# TFT_Adapter_Board.net
KiCad netlist of a schematic drawn in Altium Designer
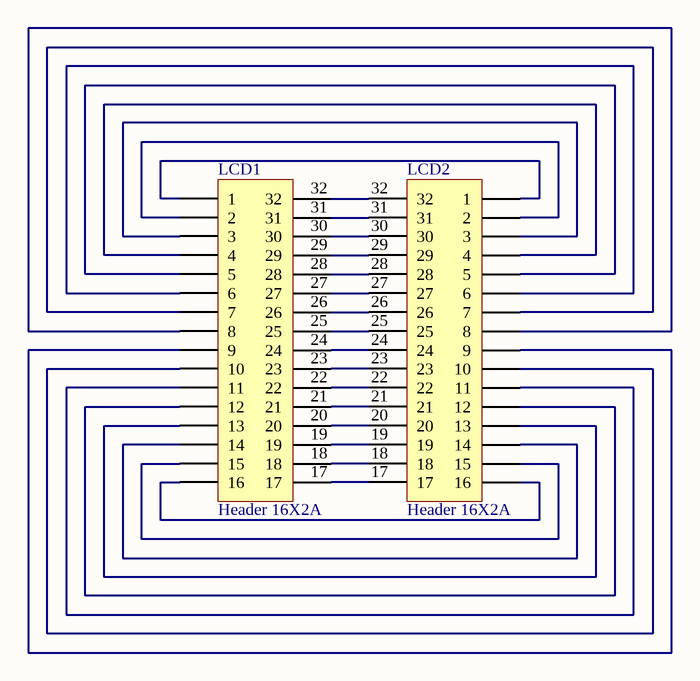
[diagram p0: TFT_Adapter_Board.SchDoc]

(export (version "E")
  (design (tool "Eeschema 10.0.6"))
  (components
    (comp (ref "LCD1")
      (value "Header 16X2A")
      (footprint "HDR2X16_CEN")
      (description "Header, 16-Pin, Dual row")
      (fields (field (name "PUBLISHER") "Altium Limited"))
      (libsource (lib "Peace的集成库") (part "Header 16X2A"))
    )
    (comp (ref "LCD2")
      (value "Header 16X2A")
      (footprint "HDR2X16_CEN")
      (description "Header, 16-Pin, Dual row")
      (fields (field (name "PUBLISHER") "Altium Limited"))
      (libsource (lib "") (part "Header 16X2A_1"))
    )
  )
  (nets
    (net (code "1") (name "Net-(LCD1-Pad1)") (class "Default")
      (node (ref "LCD1") (pin "1") (pinfunction "1_1") (pintype "passive"))
      (node (ref "LCD2") (pin "1") (pinfunction "1_1") (pintype "passive"))
    )
    (net (code "2") (name "Net-(LCD1-Pad2)") (class "Default")
      (node (ref "LCD1") (pin "2") (pinfunction "2_2") (pintype "passive"))
      (node (ref "LCD2") (pin "2") (pinfunction "2_2") (pintype "passive"))
    )
    (net (code "3") (name "Net-(LCD1-Pad3)") (class "Default")
      (node (ref "LCD1") (pin "3") (pinfunction "3_3") (pintype "passive"))
      (node (ref "LCD2") (pin "3") (pinfunction "3_3") (pintype "passive"))
    )
    (net (code "4") (name "Net-(LCD1-Pad4)") (class "Default")
      (node (ref "LCD1") (pin "4") (pinfunction "4_4") (pintype "passive"))
      (node (ref "LCD2") (pin "4") (pinfunction "4_4") (pintype "passive"))
    )
    (net (code "5") (name "Net-(LCD1-Pad5)") (class "Default")
      (node (ref "LCD1") (pin "5") (pinfunction "5_5") (pintype "passive"))
      (node (ref "LCD2") (pin "5") (pinfunction "5_5") (pintype "passive"))
    )
    (net (code "6") (name "Net-(LCD1-Pad6)") (class "Default")
      (node (ref "LCD1") (pin "6") (pinfunction "6_6") (pintype "passive"))
      (node (ref "LCD2") (pin "6") (pinfunction "6_6") (pintype "passive"))
    )
    (net (code "7") (name "Net-(LCD1-Pad7)") (class "Default")
      (node (ref "LCD1") (pin "7") (pinfunction "7_7") (pintype "passive"))
      (node (ref "LCD2") (pin "7") (pinfunction "7_7") (pintype "passive"))
    )
    (net (code "8") (name "Net-(LCD1-Pad8)") (class "Default")
      (node (ref "LCD1") (pin "8") (pinfunction "8_8") (pintype "passive"))
      (node (ref "LCD2") (pin "8") (pinfunction "8_8") (pintype "passive"))
    )
    (net (code "9") (name "Net-(LCD1-Pad9)") (class "Default")
      (node (ref "LCD1") (pin "9") (pinfunction "9_9") (pintype "passive"))
      (node (ref "LCD2") (pin "9") (pinfunction "9_9") (pintype "passive"))
    )
    (net (code "10") (name "Net-(LCD1-Pad10)") (class "Default")
      (node (ref "LCD1") (pin "10") (pinfunction "10_10") (pintype "passive"))
      (node (ref "LCD2") (pin "10") (pinfunction "10_10") (pintype "passive"))
    )
    (net (code "11") (name "Net-(LCD1-Pad11)") (class "Default")
      (node (ref "LCD1") (pin "11") (pinfunction "11_11") (pintype "passive"))
      (node (ref "LCD2") (pin "11") (pinfunction "11_11") (pintype "passive"))
    )
    (net (code "12") (name "Net-(LCD1-Pad12)") (class "Default")
      (node (ref "LCD1") (pin "12") (pinfunction "12_12") (pintype "passive"))
      (node (ref "LCD2") (pin "12") (pinfunction "12_12") (pintype "passive"))
    )
    (net (code "13") (name "Net-(LCD1-Pad13)") (class "Default")
      (node (ref "LCD1") (pin "13") (pinfunction "13_13") (pintype "passive"))
      (node (ref "LCD2") (pin "13") (pinfunction "13_13") (pintype "passive"))
    )
    (net (code "14") (name "Net-(LCD1-Pad14)") (class "Default")
      (node (ref "LCD1") (pin "14") (pinfunction "14_14") (pintype "passive"))
      (node (ref "LCD2") (pin "14") (pinfunction "14_14") (pintype "passive"))
    )
    (net (code "15") (name "Net-(LCD1-Pad15)") (class "Default")
      (node (ref "LCD1") (pin "15") (pinfunction "15_15") (pintype "passive"))
      (node (ref "LCD2") (pin "15") (pinfunction "15_15") (pintype "passive"))
    )
    (net (code "16") (name "Net-(LCD1-Pad16)") (class "Default")
      (node (ref "LCD1") (pin "16") (pinfunction "16_16") (pintype "passive"))
      (node (ref "LCD2") (pin "16") (pinfunction "16_16") (pintype "passive"))
    )
    (net (code "17") (name "Net-(LCD1-Pad17)") (class "Default")
      (node (ref "LCD1") (pin "17") (pinfunction "17_17") (pintype "passive"))
      (node (ref "LCD2") (pin "17") (pinfunction "17_17") (pintype "passive"))
    )
    (net (code "18") (name "Net-(LCD1-Pad18)") (class "Default")
      (node (ref "LCD1") (pin "18") (pinfunction "18_18") (pintype "passive"))
      (node (ref "LCD2") (pin "18") (pinfunction "18_18") (pintype "passive"))
    )
    (net (code "19") (name "Net-(LCD1-Pad19)") (class "Default")
      (node (ref "LCD1") (pin "19") (pinfunction "19_19") (pintype "passive"))
      (node (ref "LCD2") (pin "19") (pinfunction "19_19") (pintype "passive"))
    )
    (net (code "20") (name "Net-(LCD1-Pad20)") (class "Default")
      (node (ref "LCD1") (pin "20") (pinfunction "20_20") (pintype "passive"))
      (node (ref "LCD2") (pin "20") (pinfunction "20_20") (pintype "passive"))
    )
    (net (code "21") (name "Net-(LCD1-Pad21)") (class "Default")
      (node (ref "LCD1") (pin "21") (pinfunction "21_21") (pintype "passive"))
      (node (ref "LCD2") (pin "21") (pinfunction "21_21") (pintype "passive"))
    )
    (net (code "22") (name "Net-(LCD1-Pad22)") (class "Default")
      (node (ref "LCD1") (pin "22") (pinfunction "22_22") (pintype "passive"))
      (node (ref "LCD2") (pin "22") (pinfunction "22_22") (pintype "passive"))
    )
    (net (code "23") (name "Net-(LCD1-Pad23)") (class "Default")
      (node (ref "LCD1") (pin "23") (pinfunction "23_23") (pintype "passive"))
      (node (ref "LCD2") (pin "23") (pinfunction "23_23") (pintype "passive"))
    )
    (net (code "24") (name "Net-(LCD1-Pad24)") (class "Default")
      (node (ref "LCD1") (pin "24") (pinfunction "24_24") (pintype "passive"))
      (node (ref "LCD2") (pin "24") (pinfunction "24_24") (pintype "passive"))
    )
    (net (code "25") (name "Net-(LCD1-Pad25)") (class "Default")
      (node (ref "LCD1") (pin "25") (pinfunction "25_25") (pintype "passive"))
      (node (ref "LCD2") (pin "25") (pinfunction "25_25") (pintype "passive"))
    )
    (net (code "26") (name "Net-(LCD1-Pad26)") (class "Default")
      (node (ref "LCD1") (pin "26") (pinfunction "26_26") (pintype "passive"))
      (node (ref "LCD2") (pin "26") (pinfunction "26_26") (pintype "passive"))
    )
    (net (code "27") (name "Net-(LCD1-Pad27)") (class "Default")
      (node (ref "LCD1") (pin "27") (pinfunction "27_27") (pintype "passive"))
      (node (ref "LCD2") (pin "27") (pinfunction "27_27") (pintype "passive"))
    )
    (net (code "28") (name "Net-(LCD1-Pad28)") (class "Default")
      (node (ref "LCD1") (pin "28") (pinfunction "28_28") (pintype "passive"))
      (node (ref "LCD2") (pin "28") (pinfunction "28_28") (pintype "passive"))
    )
    (net (code "29") (name "Net-(LCD1-Pad29)") (class "Default")
      (node (ref "LCD1") (pin "29") (pinfunction "29_29") (pintype "passive"))
      (node (ref "LCD2") (pin "29") (pinfunction "29_29") (pintype "passive"))
    )
    (net (code "30") (name "Net-(LCD1-Pad30)") (class "Default")
      (node (ref "LCD1") (pin "30") (pinfunction "30_30") (pintype "passive"))
      (node (ref "LCD2") (pin "30") (pinfunction "30_30") (pintype "passive"))
    )
    (net (code "31") (name "Net-(LCD1-Pad31)") (class "Default")
      (node (ref "LCD1") (pin "31") (pinfunction "31_31") (pintype "passive"))
      (node (ref "LCD2") (pin "31") (pinfunction "31_31") (pintype "passive"))
    )
    (net (code "32") (name "Net-(LCD1-Pad32)") (class "Default")
      (node (ref "LCD1") (pin "32") (pinfunction "32_32") (pintype "passive"))
      (node (ref "LCD2") (pin "32") (pinfunction "32_32") (pintype "passive"))
    )
  )
)
